# HotFireBoard.net
KiCad netlist of a schematic drawn in EAGLE
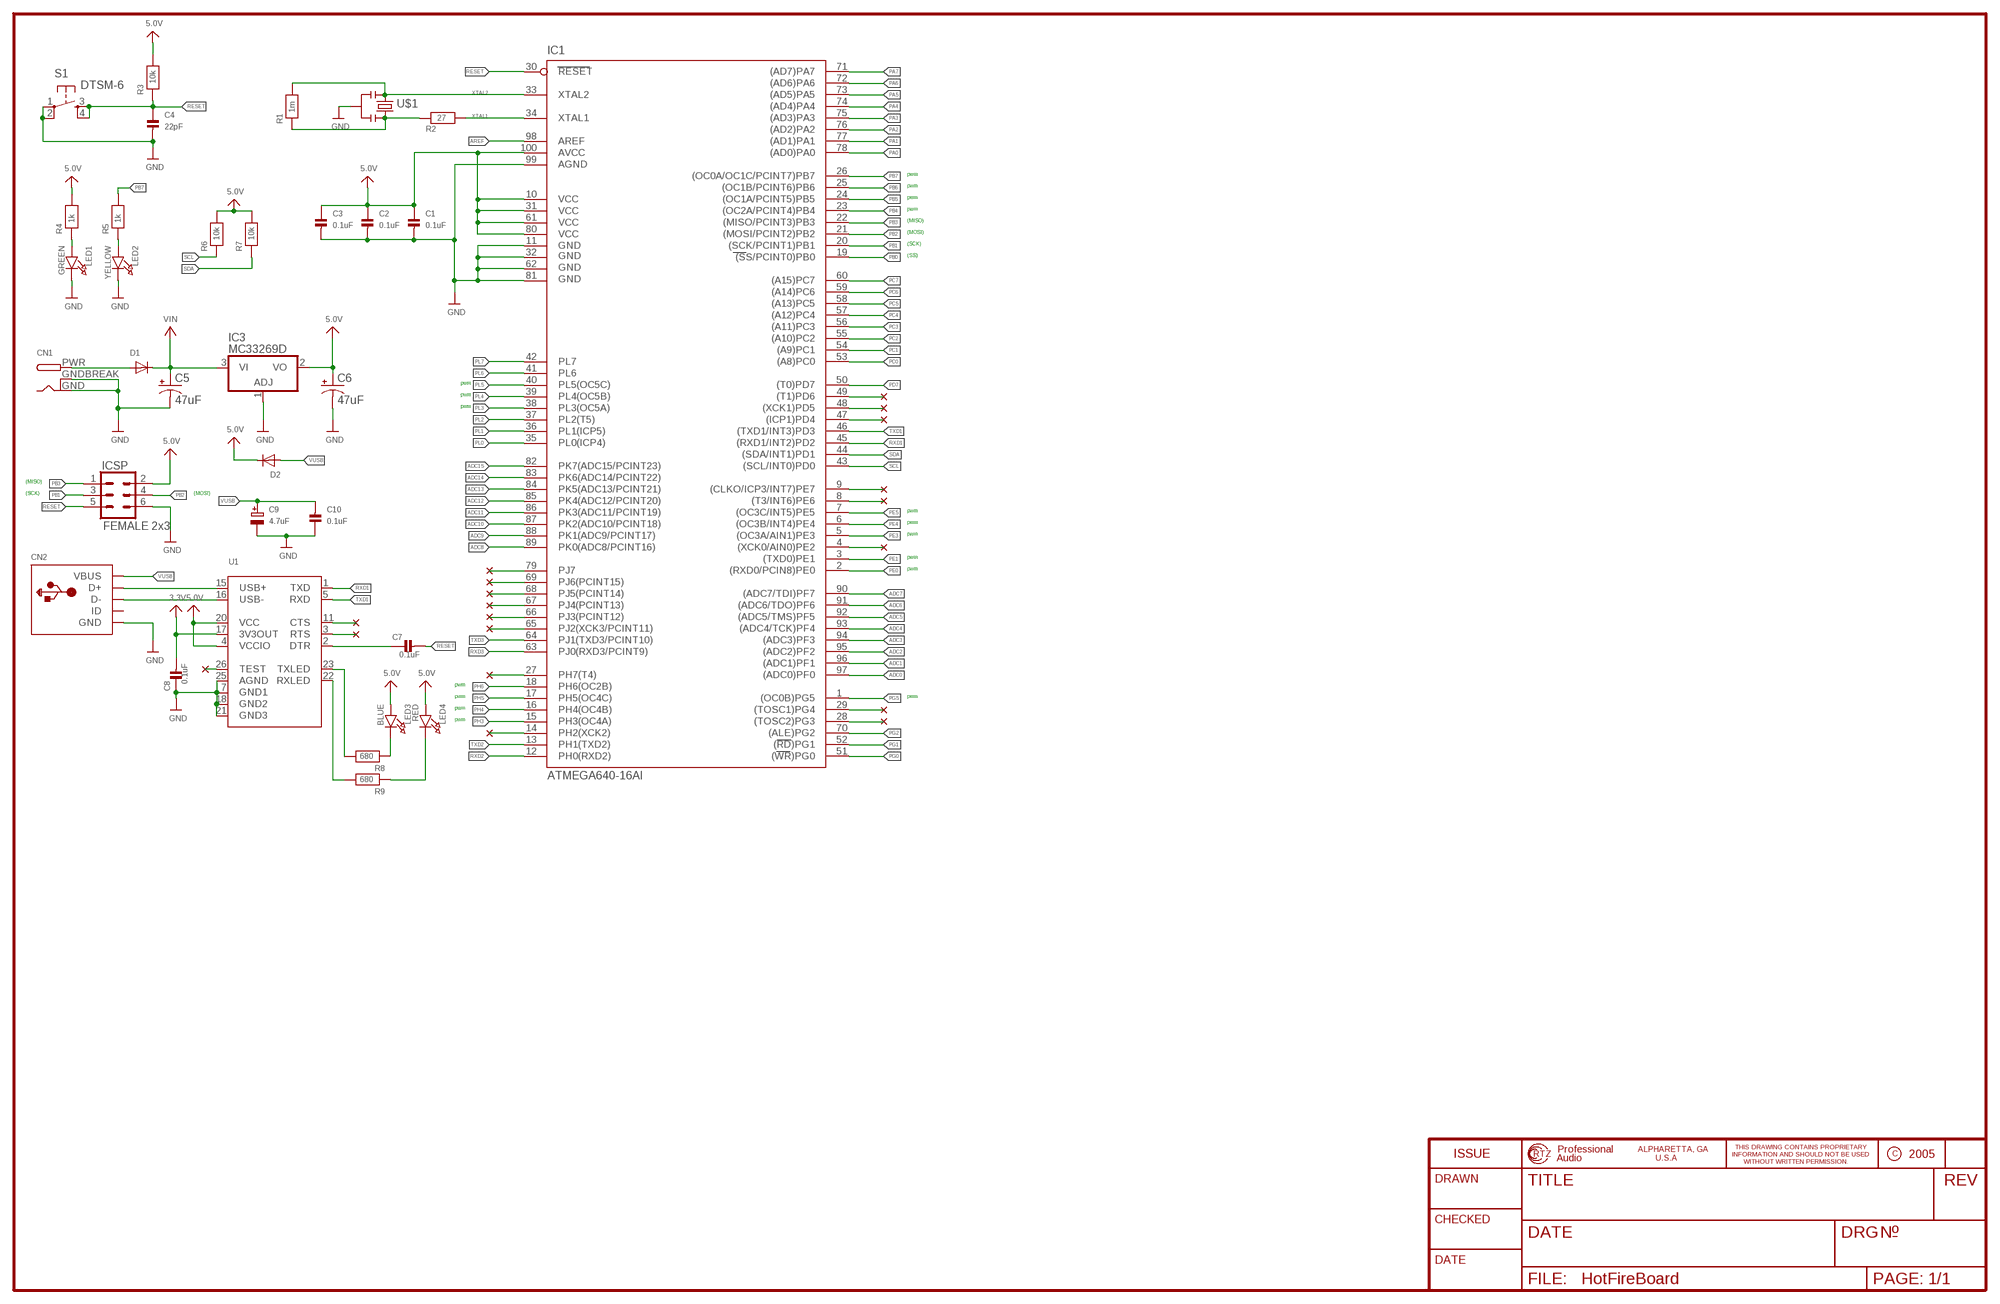
[diagram p0: schematic, sheet 1]

(export (version "E")
  (design (tool "Eeschema 10.0.6"))
  (components
    (comp (ref "C1")
      (value "0.1uF")
      (footprint "eagle-import:0805")
      (libsource (lib "eagle-import") (part "CAP_CERAMIC0805"))
    )
    (comp (ref "C2")
      (value "0.1uF")
      (footprint "eagle-import:0805")
      (libsource (lib "eagle-import") (part "CAP_CERAMIC0805"))
    )
    (comp (ref "C3")
      (value "0.1uF")
      (footprint "eagle-import:0805")
      (libsource (lib "eagle-import") (part "CAP_CERAMIC0805"))
    )
    (comp (ref "C4")
      (value "22pF")
      (footprint "eagle-import:0805")
      (libsource (lib "eagle-import") (part "CAP_CERAMIC0805"))
    )
    (comp (ref "C5")
      (value "47uF")
      (footprint "eagle-import:PANASONIC_D")
      (libsource (lib "eagle-import") (part "CPOL-USD"))
    )
    (comp (ref "C6")
      (value "47uF")
      (footprint "eagle-import:PANASONIC_D")
      (libsource (lib "eagle-import") (part "CPOL-USD"))
    )
    (comp (ref "C7")
      (value "0.1uF")
      (footprint "eagle-import:0805")
      (libsource (lib "eagle-import") (part "CAP_CERAMIC0805"))
    )
    (comp (ref "C8")
      (value "0.1uF")
      (footprint "eagle-import:0805")
      (libsource (lib "eagle-import") (part "CAP_CERAMIC0805"))
    )
    (comp (ref "C9")
      (value "4.7uF")
      (footprint "eagle-import:EIA7343-31_D-W")
      (libsource (lib "eagle-import") (part "CAP_TANTALUMD/7343_WAVE"))
    )
    (comp (ref "C10")
      (value "0.1uF")
      (footprint "eagle-import:0805")
      (libsource (lib "eagle-import") (part "CAP_CERAMIC0805"))
    )
    (comp (ref "CN1")
      (value "DCBARRELPTH")
      (footprint "eagle-import:DCJACK_2MM_PTH")
      (libsource (lib "eagle-import") (part "DCBARRELPTH"))
    )
    (comp (ref "CN2")
      (value "USBMINIB")
      (footprint "eagle-import:USB-MINIB")
      (libsource (lib "eagle-import") (part "USBMINIB"))
    )
    (comp (ref "D1")
      (value "DIODESOD-123")
      (footprint "eagle-import:SOD-123")
      (libsource (lib "eagle-import") (part "DIODESOD-123"))
    )
    (comp (ref "D2")
      (value "DIODESOD-123")
      (footprint "eagle-import:SOD-123")
      (libsource (lib "eagle-import") (part "DIODESOD-123"))
    )
    (comp (ref "IC1")
      (value "ATMEGA640-16AI")
      (footprint "eagle-import:TQFP100")
      (libsource (lib "eagle-import") (part "ATMEGAAI640-16"))
    )
    (comp (ref "IC3")
      (value "MC33269D")
      (footprint "eagle-import:DPACK")
      (libsource (lib "eagle-import") (part "MC33269?D"))
    )
    (comp (ref "ICSP")
      (value "FEMALE 2x3")
      (footprint "eagle-import:2X3")
      (libsource (lib "eagle-import") (part "CONN_03X2FEMALE"))
    )
    (comp (ref "LED1")
      (value "GREEN")
      (footprint "eagle-import:CHIPLED_0805")
      (libsource (lib "eagle-import") (part "LED0805"))
    )
    (comp (ref "LED2")
      (value "YELLOW")
      (footprint "eagle-import:CHIPLED_0805")
      (libsource (lib "eagle-import") (part "LED0805"))
    )
    (comp (ref "LED3")
      (value "BLUE")
      (footprint "eagle-import:CHIPLED_0805")
      (libsource (lib "eagle-import") (part "LED0805"))
    )
    (comp (ref "LED4")
      (value "RED")
      (footprint "eagle-import:CHIPLED_0805")
      (libsource (lib "eagle-import") (part "LED0805"))
    )
    (comp (ref "R1")
      (value "1m")
      (footprint "eagle-import:0805")
      (libsource (lib "eagle-import") (part "RESISTOR0805"))
    )
    (comp (ref "R2")
      (value "27")
      (footprint "eagle-import:0805")
      (libsource (lib "eagle-import") (part "RESISTOR0805"))
    )
    (comp (ref "R3")
      (value "10k")
      (footprint "eagle-import:0805")
      (libsource (lib "eagle-import") (part "RESISTOR0805"))
    )
    (comp (ref "R4")
      (value "1k")
      (footprint "eagle-import:0805")
      (libsource (lib "eagle-import") (part "RESISTOR0805"))
    )
    (comp (ref "R5")
      (value "1k")
      (footprint "eagle-import:0805")
      (libsource (lib "eagle-import") (part "RESISTOR0805"))
    )
    (comp (ref "R6")
      (value "10k")
      (footprint "eagle-import:0805")
      (libsource (lib "eagle-import") (part "RESISTOR0805"))
    )
    (comp (ref "R7")
      (value "10k")
      (footprint "eagle-import:0805")
      (libsource (lib "eagle-import") (part "RESISTOR0805"))
    )
    (comp (ref "R8")
      (value "680")
      (footprint "eagle-import:0805")
      (libsource (lib "eagle-import") (part "RESISTOR0805"))
    )
    (comp (ref "R9")
      (value "680")
      (footprint "eagle-import:0805")
      (libsource (lib "eagle-import") (part "RESISTOR0805"))
    )
    (comp (ref "S1")
      (value "DTSM-6")
      (footprint "eagle-import:DTSM-6")
      (libsource (lib "eagle-import") (part "DTSM-6"))
    )
    (comp (ref "U$1")
      (value "RESONATORSMD")
      (footprint "eagle-import:RESONATOR-SMD")
      (libsource (lib "eagle-import") (part "RESONATORSMD"))
    )
    (comp (ref "U$6") (value "NC") (footprint "eagle-import:NC") (libsource (lib "eagle-import") (part "NC")))
    (comp (ref "U$7") (value "NC") (footprint "eagle-import:NC") (libsource (lib "eagle-import") (part "NC")))
    (comp (ref "U$8") (value "NC") (footprint "eagle-import:NC") (libsource (lib "eagle-import") (part "NC")))
    (comp (ref "U$9") (value "NC") (footprint "eagle-import:NC") (libsource (lib "eagle-import") (part "NC")))
    (comp (ref "U$10")
      (value "NC")
      (footprint "eagle-import:NC")
      (libsource (lib "eagle-import") (part "NC"))
    )
    (comp (ref "U$11")
      (value "NC")
      (footprint "eagle-import:NC")
      (libsource (lib "eagle-import") (part "NC"))
    )
    (comp (ref "U$12")
      (value "NC")
      (footprint "eagle-import:NC")
      (libsource (lib "eagle-import") (part "NC"))
    )
    (comp (ref "U$13")
      (value "NC")
      (footprint "eagle-import:NC")
      (libsource (lib "eagle-import") (part "NC"))
    )
    (comp (ref "U$14")
      (value "NC")
      (footprint "eagle-import:NC")
      (libsource (lib "eagle-import") (part "NC"))
    )
    (comp (ref "U$15")
      (value "NC")
      (footprint "eagle-import:NC")
      (libsource (lib "eagle-import") (part "NC"))
    )
    (comp (ref "U$16")
      (value "NC")
      (footprint "eagle-import:NC")
      (libsource (lib "eagle-import") (part "NC"))
    )
    (comp (ref "U$17")
      (value "NC")
      (footprint "eagle-import:NC")
      (libsource (lib "eagle-import") (part "NC"))
    )
    (comp (ref "U$18")
      (value "NC")
      (footprint "eagle-import:NC")
      (libsource (lib "eagle-import") (part "NC"))
    )
    (comp (ref "U$19")
      (value "NC")
      (footprint "eagle-import:NC")
      (libsource (lib "eagle-import") (part "NC"))
    )
    (comp (ref "U$20")
      (value "NC")
      (footprint "eagle-import:NC")
      (libsource (lib "eagle-import") (part "NC"))
    )
    (comp (ref "U$21")
      (value "NC")
      (footprint "eagle-import:NC")
      (libsource (lib "eagle-import") (part "NC"))
    )
    (comp (ref "U$37")
      (value "NC")
      (footprint "eagle-import:NC")
      (libsource (lib "eagle-import") (part "NC"))
    )
    (comp (ref "U$38")
      (value "NC")
      (footprint "eagle-import:NC")
      (libsource (lib "eagle-import") (part "NC"))
    )
    (comp (ref "U$42")
      (value "NC")
      (footprint "eagle-import:NC")
      (libsource (lib "eagle-import") (part "NC"))
    )
    (comp (ref "U1")
      (value "FT232RLSSOP28")
      (footprint "eagle-import:SSOP28DB")
      (libsource (lib "eagle-import") (part "FT232RLSSOP28"))
    )
  )
  (nets
    (net (code "1") (name "/XTAL1") (class "Default")
      (node (ref "IC1") (pin "34") (pinfunction "XTAL1_34") (pintype "input"))
      (node (ref "R2") (pin "1") (pinfunction "1_1") (pintype "passive"))
    )
    (net (code "2") (name "/XTAL2") (class "Default")
      (node (ref "IC1") (pin "33") (pinfunction "XTAL2_33") (pintype "output"))
      (node (ref "R1") (pin "2") (pinfunction "2_2") (pintype "passive"))
      (node (ref "U$1") (pin "1") (pinfunction "1_1") (pintype "passive"))
    )
    (net (code "3") (name "3.3V") (class "Default")
      (node (ref "C8") (pin "2") (pinfunction "P$2_2") (pintype "passive"))
      (node (ref "U1") (pin "17") (pinfunction "3V3OUT_17") (pintype "power_in"))
    )
    (net (code "4") (name "5.0V") (class "Default")
      (node (ref "C1") (pin "1") (pinfunction "P$1_1") (pintype "passive"))
      (node (ref "C2") (pin "1") (pinfunction "P$1_1") (pintype "passive"))
      (node (ref "C3") (pin "1") (pinfunction "P$1_1") (pintype "passive"))
      (node (ref "C6") (pin "+") (pinfunction "+_+") (pintype "passive"))
      (node (ref "D2") (pin "C") (pinfunction "C_C") (pintype "passive"))
      (node (ref "IC1") (pin "10") (pinfunction "VCC_10") (pintype "power_in"))
      (node (ref "IC1") (pin "100") (pinfunction "AVCC_100") (pintype "power_in"))
      (node (ref "IC1") (pin "31") (pinfunction "VCC1_31") (pintype "power_in"))
      (node (ref "IC1") (pin "61") (pinfunction "VCC2_61") (pintype "power_in"))
      (node (ref "IC1") (pin "80") (pinfunction "VCC3_80") (pintype "power_in"))
      (node (ref "IC3") (pin "2") (pinfunction "VO_2") (pintype "passive"))
      (node (ref "ICSP") (pin "2") (pinfunction "2_2") (pintype "bidirectional"))
      (node (ref "LED3") (pin "A") (pinfunction "A_A") (pintype "passive"))
      (node (ref "LED4") (pin "A") (pinfunction "A_A") (pintype "passive"))
      (node (ref "R3") (pin "2") (pinfunction "2_2") (pintype "passive"))
      (node (ref "R4") (pin "2") (pinfunction "2_2") (pintype "passive"))
      (node (ref "R6") (pin "2") (pinfunction "2_2") (pintype "passive"))
      (node (ref "R7") (pin "2") (pinfunction "2_2") (pintype "passive"))
      (node (ref "U1") (pin "20") (pinfunction "VCC_20") (pintype "power_in"))
      (node (ref "U1") (pin "4") (pinfunction "VCCIO_4") (pintype "power_in"))
    )
    (net (code "5") (name "ADC0") (class "Default")
      (node (ref "IC1") (pin "97") (pinfunction "(ADC0)PF0_97") (pintype "bidirectional"))
    )
    (net (code "6") (name "ADC1") (class "Default")
      (node (ref "IC1") (pin "96") (pinfunction "(ADC1)PF1_96") (pintype "bidirectional"))
    )
    (net (code "7") (name "ADC2") (class "Default")
      (node (ref "IC1") (pin "95") (pinfunction "(ADC2)PF2_95") (pintype "bidirectional"))
    )
    (net (code "8") (name "ADC3") (class "Default")
      (node (ref "IC1") (pin "94") (pinfunction "(ADC3)PF3_94") (pintype "bidirectional"))
    )
    (net (code "9") (name "ADC4") (class "Default")
      (node (ref "IC1") (pin "93") (pinfunction "(ADC4/TCK)PF4_93") (pintype "bidirectional"))
    )
    (net (code "10") (name "ADC5") (class "Default")
      (node (ref "IC1") (pin "92") (pinfunction "(ADC5/TMS)PF5_92") (pintype "bidirectional"))
    )
    (net (code "11") (name "ADC6") (class "Default")
      (node (ref "IC1") (pin "91") (pinfunction "(ADC6/TDO)PF6_91") (pintype "bidirectional"))
    )
    (net (code "12") (name "ADC7") (class "Default")
      (node (ref "IC1") (pin "90") (pinfunction "(ADC7/TDI)PF7_90") (pintype "bidirectional"))
    )
    (net (code "13") (name "ADC8") (class "Default")
      (node (ref "IC1") (pin "89") (pinfunction "PK0(ADC8/PCINT16)_89") (pintype "bidirectional"))
    )
    (net (code "14") (name "ADC9") (class "Default")
      (node (ref "IC1") (pin "88") (pinfunction "PK1(ADC9/PCINT17)_88") (pintype "bidirectional"))
    )
    (net (code "15") (name "ADC10") (class "Default")
      (node (ref "IC1") (pin "87") (pinfunction "PK2(ADC10/PCINT18)_87") (pintype "bidirectional"))
    )
    (net (code "16") (name "ADC11") (class "Default")
      (node (ref "IC1") (pin "86") (pinfunction "PK3(ADC11/PCINT19)_86") (pintype "bidirectional"))
    )
    (net (code "17") (name "ADC12") (class "Default")
      (node (ref "IC1") (pin "85") (pinfunction "PK4(ADC12/PCINT20)_85") (pintype "bidirectional"))
    )
    (net (code "18") (name "ADC13") (class "Default")
      (node (ref "IC1") (pin "84") (pinfunction "PK5(ADC13/PCINT21)_84") (pintype "bidirectional"))
    )
    (net (code "19") (name "ADC14") (class "Default")
      (node (ref "IC1") (pin "83") (pinfunction "PK6(ADC14/PCINT22)_83") (pintype "bidirectional"))
    )
    (net (code "20") (name "ADC15") (class "Default")
      (node (ref "IC1") (pin "82") (pinfunction "PK7(ADC15/PCINT23)_82") (pintype "bidirectional"))
    )
    (net (code "21") (name "AREF") (class "Default")
      (node (ref "IC1") (pin "98") (pinfunction "AREF_98") (pintype "bidirectional"))
    )
    (net (code "22") (name "GND") (class "Default")
      (node (ref "C1") (pin "2") (pinfunction "P$2_2") (pintype "passive"))
      (node (ref "C10") (pin "1") (pinfunction "P$1_1") (pintype "passive"))
      (node (ref "C2") (pin "2") (pinfunction "P$2_2") (pintype "passive"))
      (node (ref "C3") (pin "2") (pinfunction "P$2_2") (pintype "passive"))
      (node (ref "C4") (pin "2") (pinfunction "P$2_2") (pintype "passive"))
      (node (ref "C5") (pin "-") (pinfunction "-_-") (pintype "passive"))
      (node (ref "C6") (pin "-") (pinfunction "-_-") (pintype "passive"))
      (node (ref "C8") (pin "1") (pinfunction "P$1_1") (pintype "passive"))
      (node (ref "C9") (pin "-") (pinfunction "-_-") (pintype "passive"))
      (node (ref "CN1") (pin "GND") (pinfunction "GND_GND") (pintype "power_in"))
      (node (ref "CN1") (pin "GNDBREAK") (pinfunction "GNDBREAK_GNDBREAK") (pintype "power_in"))
      (node (ref "CN2") (pin "GND") (pinfunction "GND_GND") (pintype "power_in"))
      (node (ref "IC1") (pin "11") (pinfunction "GND_11") (pintype "power_in"))
      (node (ref "IC1") (pin "32") (pinfunction "GND1_32") (pintype "power_in"))
      (node (ref "IC1") (pin "62") (pinfunction "GND2_62") (pintype "power_in"))
      (node (ref "IC1") (pin "81") (pinfunction "GND3_81") (pintype "power_in"))
      (node (ref "IC1") (pin "99") (pinfunction "AGND_99") (pintype "power_in"))
      (node (ref "IC3") (pin "1") (pinfunction "ADJ_1") (pintype "input"))
      (node (ref "ICSP") (pin "6") (pinfunction "6_6") (pintype "bidirectional"))
      (node (ref "LED1") (pin "C") (pinfunction "C_C") (pintype "passive"))
      (node (ref "LED2") (pin "C") (pinfunction "C_C") (pintype "passive"))
      (node (ref "S1") (pin "1") (pinfunction "1_1") (pintype "passive"))
      (node (ref "S1") (pin "2") (pinfunction "2_2") (pintype "passive"))
      (node (ref "U$1") (pin "2") (pinfunction "2_2") (pintype "passive"))
      (node (ref "U1") (pin "18") (pinfunction "GND2_18") (pintype "power_in"))
      (node (ref "U1") (pin "21") (pinfunction "GND3_21") (pintype "power_in"))
      (node (ref "U1") (pin "25") (pinfunction "AGND_25") (pintype "power_in"))
      (node (ref "U1") (pin "7") (pinfunction "GND1_7") (pintype "power_in"))
    )
    (net (code "23") (name "Net-(C7-P$1)") (class "Default")
      (node (ref "C7") (pin "1") (pinfunction "P$1_1") (pintype "passive"))
      (node (ref "U1") (pin "2") (pinfunction "DTR_2") (pintype "bidirectional"))
    )
    (net (code "24") (name "Net-(CN1-PadPWR)") (class "Default")
      (node (ref "CN1") (pin "PWR") (pinfunction "PWR_PWR") (pintype "power_in"))
      (node (ref "D1") (pin "A") (pinfunction "A_A") (pintype "passive"))
    )
    (net (code "25") (name "Net-(LED1-PadA)") (class "Default")
      (node (ref "LED1") (pin "A") (pinfunction "A_A") (pintype "passive"))
      (node (ref "R4") (pin "1") (pinfunction "1_1") (pintype "passive"))
    )
    (net (code "26") (name "Net-(LED2-PadA)") (class "Default")
      (node (ref "LED2") (pin "A") (pinfunction "A_A") (pintype "passive"))
      (node (ref "R5") (pin "1") (pinfunction "1_1") (pintype "passive"))
    )
    (net (code "27") (name "Net-(LED3-PadC)") (class "Default")
      (node (ref "LED3") (pin "C") (pinfunction "C_C") (pintype "passive"))
      (node (ref "R8") (pin "1") (pinfunction "1_1") (pintype "passive"))
    )
    (net (code "28") (name "Net-(LED4-PadC)") (class "Default")
      (node (ref "LED4") (pin "C") (pinfunction "C_C") (pintype "passive"))
      (node (ref "R9") (pin "1") (pinfunction "1_1") (pintype "passive"))
    )
    (net (code "29") (name "Net-(R1-Pad1)") (class "Default")
      (node (ref "R1") (pin "1") (pinfunction "1_1") (pintype "passive"))
      (node (ref "R2") (pin "2") (pinfunction "2_2") (pintype "passive"))
      (node (ref "U$1") (pin "3") (pinfunction "3_3") (pintype "passive"))
    )
    (net (code "30") (name "Net-(U1-RXLED)") (class "Default")
      (node (ref "R9") (pin "2") (pinfunction "2_2") (pintype "passive"))
      (node (ref "U1") (pin "22") (pinfunction "RXLED_22") (pintype "bidirectional"))
    )
    (net (code "31") (name "Net-(U1-TXLED)") (class "Default")
      (node (ref "R8") (pin "2") (pinfunction "2_2") (pintype "passive"))
      (node (ref "U1") (pin "23") (pinfunction "TXLED_23") (pintype "bidirectional"))
    )
    (net (code "32") (name "Net-(U1-USB+)") (class "Default")
      (node (ref "CN2") (pin "D+") (pinfunction "D+_D+") (pintype "bidirectional"))
      (node (ref "U1") (pin "15") (pinfunction "USB+_15") (pintype "bidirectional"))
    )
    (net (code "33") (name "Net-(U1-USB-)") (class "Default")
      (node (ref "CN2") (pin "D-") (pinfunction "D-_D-") (pintype "bidirectional"))
      (node (ref "U1") (pin "16") (pinfunction "USB-_16") (pintype "bidirectional"))
    )
    (net (code "34") (name "PA0") (class "Default")
      (node (ref "IC1") (pin "78") (pinfunction "(AD0)PA0_78") (pintype "bidirectional"))
    )
    (net (code "35") (name "PA1") (class "Default")
      (node (ref "IC1") (pin "77") (pinfunction "(AD1)PA1_77") (pintype "bidirectional"))
    )
    (net (code "36") (name "PA2") (class "Default")
      (node (ref "IC1") (pin "76") (pinfunction "(AD2)PA2_76") (pintype "bidirectional"))
    )
    (net (code "37") (name "PA3") (class "Default")
      (node (ref "IC1") (pin "75") (pinfunction "(AD3)PA3_75") (pintype "bidirectional"))
    )
    (net (code "38") (name "PA4") (class "Default")
      (node (ref "IC1") (pin "74") (pinfunction "(AD4)PA4_74") (pintype "bidirectional"))
    )
    (net (code "39") (name "PA5") (class "Default")
      (node (ref "IC1") (pin "73") (pinfunction "(AD5)PA5_73") (pintype "bidirectional"))
    )
    (net (code "40") (name "PA6") (class "Default")
      (node (ref "IC1") (pin "72") (pinfunction "(AD6)PA6_72") (pintype "bidirectional"))
    )
    (net (code "41") (name "PA7") (class "Default")
      (node (ref "IC1") (pin "71") (pinfunction "(AD7)PA7_71") (pintype "bidirectional"))
    )
    (net (code "42") (name "PB0") (class "Default")
      (node (ref "IC1") (pin "19") (pinfunction "(SS/PCINT0)PB0_19") (pintype "bidirectional"))
    )
    (net (code "43") (name "PB1") (class "Default")
      (node (ref "IC1") (pin "20") (pinfunction "(SCK/PCINT1)PB1_20") (pintype "bidirectional"))
      (node (ref "ICSP") (pin "3") (pinfunction "3_3") (pintype "bidirectional"))
    )
    (net (code "44") (name "PB2") (class "Default")
      (node (ref "IC1") (pin "21") (pinfunction "(MOSI/PCINT2)PB2_21") (pintype "bidirectional"))
      (node (ref "ICSP") (pin "4") (pinfunction "4_4") (pintype "bidirectional"))
    )
    (net (code "45") (name "PB3") (class "Default")
      (node (ref "IC1") (pin "22") (pinfunction "(MISO/PCINT3)PB3_22") (pintype "bidirectional"))
      (node (ref "ICSP") (pin "1") (pinfunction "1_1") (pintype "bidirectional"))
    )
    (net (code "46") (name "PB4") (class "Default")
      (node (ref "IC1") (pin "23") (pinfunction "(OC2A/PCINT4)PB4_23") (pintype "bidirectional"))
    )
    (net (code "47") (name "PB5") (class "Default")
      (node (ref "IC1") (pin "24") (pinfunction "(OC1A/PCINT5)PB5_24") (pintype "bidirectional"))
    )
    (net (code "48") (name "PB6") (class "Default")
      (node (ref "IC1") (pin "25") (pinfunction "(OC1B/PCINT6)PB6_25") (pintype "bidirectional"))
    )
    (net (code "49") (name "PB7") (class "Default")
      (node (ref "IC1") (pin "26") (pinfunction "(OC0A/OC1C/PCINT7)PB7_26") (pintype "bidirectional"))
      (node (ref "R5") (pin "2") (pinfunction "2_2") (pintype "passive"))
    )
    (net (code "50") (name "PC0") (class "Default")
      (node (ref "IC1") (pin "53") (pinfunction "(A8)PC0_53") (pintype "bidirectional"))
    )
    (net (code "51") (name "PC1") (class "Default")
      (node (ref "IC1") (pin "54") (pinfunction "(A9)PC1_54") (pintype "bidirectional"))
    )
    (net (code "52") (name "PC2") (class "Default")
      (node (ref "IC1") (pin "55") (pinfunction "(A10)PC2_55") (pintype "bidirectional"))
    )
    (net (code "53") (name "PC3") (class "Default")
      (node (ref "IC1") (pin "56") (pinfunction "(A11)PC3_56") (pintype "bidirectional"))
    )
    (net (code "54") (name "PC4") (class "Default")
      (node (ref "IC1") (pin "57") (pinfunction "(A12)PC4_57") (pintype "bidirectional"))
    )
    (net (code "55") (name "PC5") (class "Default")
      (node (ref "IC1") (pin "58") (pinfunction "(A13)PC5_58") (pintype "bidirectional"))
    )
    (net (code "56") (name "PC6") (class "Default")
      (node (ref "IC1") (pin "59") (pinfunction "(A14)PC6_59") (pintype "bidirectional"))
    )
    (net (code "57") (name "PC7") (class "Default")
      (node (ref "IC1") (pin "60") (pinfunction "(A15)PC7_60") (pintype "bidirectional"))
    )
    (net (code "58") (name "PD7") (class "Default")
      (node (ref "IC1") (pin "50") (pinfunction "(T0)PD7_50") (pintype "bidirectional"))
    )
    (net (code "59") (name "PE0") (class "Default")
      (node (ref "IC1") (pin "2") (pinfunction "(RXD0/PCIN8)PE0_2") (pintype "bidirectional"))
    )
    (net (code "60") (name "PE1") (class "Default")
      (node (ref "IC1") (pin "3") (pinfunction "(TXD0)PE1_3") (pintype "bidirectional"))
    )
    (net (code "61") (name "PE3") (class "Default")
      (node (ref "IC1") (pin "5") (pinfunction "(OC3A/AIN1)PE3_5") (pintype "bidirectional"))
    )
    (net (code "62") (name "PE4") (class "Default")
      (node (ref "IC1") (pin "6") (pinfunction "(OC3B/INT4)PE4_6") (pintype "bidirectional"))
    )
    (net (code "63") (name "PE5") (class "Default")
      (node (ref "IC1") (pin "7") (pinfunction "(OC3C/INT5)PE5_7") (pintype "bidirectional"))
    )
    (net (code "64") (name "PG0") (class "Default")
      (node (ref "IC1") (pin "51") (pinfunction "(WR)PG0_51") (pintype "bidirectional"))
    )
    (net (code "65") (name "PG1") (class "Default")
      (node (ref "IC1") (pin "52") (pinfunction "(RD)PG1_52") (pintype "bidirectional"))
    )
    (net (code "66") (name "PG2") (class "Default")
      (node (ref "IC1") (pin "70") (pinfunction "(ALE)PG2_70") (pintype "bidirectional"))
    )
    (net (code "67") (name "PG5") (class "Default")
      (node (ref "IC1") (pin "1") (pinfunction "(OC0B)PG5_1") (pintype "bidirectional"))
    )
    (net (code "68") (name "PH3") (class "Default")
      (node (ref "IC1") (pin "15") (pinfunction "PH3(OC4A)_15") (pintype "bidirectional"))
    )
    (net (code "69") (name "PH4") (class "Default")
      (node (ref "IC1") (pin "16") (pinfunction "PH4(OC4B)_16") (pintype "bidirectional"))
    )
    (net (code "70") (name "PH5") (class "Default")
      (node (ref "IC1") (pin "17") (pinfunction "PH5(OC4C)_17") (pintype "bidirectional"))
    )
    (net (code "71") (name "PH6") (class "Default")
      (node (ref "IC1") (pin "18") (pinfunction "PH6(OC2B)_18") (pintype "bidirectional"))
    )
    (net (code "72") (name "PL0") (class "Default")
      (node (ref "IC1") (pin "35") (pinfunction "PL0(ICP4)_35") (pintype "bidirectional"))
    )
    (net (code "73") (name "PL1") (class "Default")
      (node (ref "IC1") (pin "36") (pinfunction "PL1(ICP5)_36") (pintype "bidirectional"))
    )
    (net (code "74") (name "PL2") (class "Default")
      (node (ref "IC1") (pin "37") (pinfunction "PL2(T5)_37") (pintype "bidirectional"))
    )
    (net (code "75") (name "PL3") (class "Default")
      (node (ref "IC1") (pin "38") (pinfunction "PL3(OC5A)_38") (pintype "bidirectional"))
    )
    (net (code "76") (name "PL4") (class "Default")
      (node (ref "IC1") (pin "39") (pinfunction "PL4(OC5B)_39") (pintype "bidirectional"))
    )
    (net (code "77") (name "PL5") (class "Default")
      (node (ref "IC1") (pin "40") (pinfunction "PL5(OC5C)_40") (pintype "bidirectional"))
    )
    (net (code "78") (name "PL6") (class "Default")
      (node (ref "IC1") (pin "41") (pinfunction "PL6_41") (pintype "bidirectional"))
    )
    (net (code "79") (name "PL7") (class "Default")
      (node (ref "IC1") (pin "42") (pinfunction "PL7_42") (pintype "bidirectional"))
    )
    (net (code "80") (name "RESET") (class "Default")
      (node (ref "C4") (pin "1") (pinfunction "P$1_1") (pintype "passive"))
      (node (ref "C7") (pin "2") (pinfunction "P$2_2") (pintype "passive"))
      (node (ref "IC1") (pin "30") (pinfunction "RESET_30") (pintype "input"))
      (node (ref "ICSP") (pin "5") (pinfunction "5_5") (pintype "bidirectional"))
      (node (ref "R3") (pin "1") (pinfunction "1_1") (pintype "passive"))
      (node (ref "S1") (pin "3") (pinfunction "3_3") (pintype "passive"))
      (node (ref "S1") (pin "4") (pinfunction "4_4") (pintype "passive"))
    )
    (net (code "81") (name "RXD1") (class "Default")
      (node (ref "IC1") (pin "45") (pinfunction "(RXD1/INT2)PD2_45") (pintype "bidirectional"))
      (node (ref "U1") (pin "1") (pinfunction "TXD_1") (pintype "output"))
    )
    (net (code "82") (name "RXD2") (class "Default")
      (node (ref "IC1") (pin "12") (pinfunction "PH0(RXD2)_12") (pintype "bidirectional"))
    )
    (net (code "83") (name "RXD3") (class "Default")
      (node (ref "IC1") (pin "63") (pinfunction "PJ0(RXD3/PCINT9)_63") (pintype "bidirectional"))
    )
    (net (code "84") (name "SCL") (class "Default")
      (node (ref "IC1") (pin "43") (pinfunction "(SCL/INT0)PD0_43") (pintype "bidirectional"))
      (node (ref "R6") (pin "1") (pinfunction "1_1") (pintype "passive"))
    )
    (net (code "85") (name "SDA") (class "Default")
      (node (ref "IC1") (pin "44") (pinfunction "(SDA/INT1)PD1_44") (pintype "bidirectional"))
      (node (ref "R7") (pin "1") (pinfunction "1_1") (pintype "passive"))
    )
    (net (code "86") (name "TXD1") (class "Default")
      (node (ref "IC1") (pin "46") (pinfunction "(TXD1/INT3)PD3_46") (pintype "bidirectional"))
      (node (ref "U1") (pin "5") (pinfunction "RXD_5") (pintype "input"))
    )
    (net (code "87") (name "TXD2") (class "Default")
      (node (ref "IC1") (pin "13") (pinfunction "PH1(TXD2)_13") (pintype "bidirectional"))
    )
    (net (code "88") (name "TXD3") (class "Default")
      (node (ref "IC1") (pin "64") (pinfunction "PJ1(TXD3/PCINT10)_64") (pintype "bidirectional"))
    )
    (net (code "89") (name "VIN") (class "Default")
      (node (ref "C5") (pin "+") (pinfunction "+_+") (pintype "passive"))
      (node (ref "D1") (pin "C") (pinfunction "C_C") (pintype "passive"))
      (node (ref "IC3") (pin "3") (pinfunction "VI_3") (pintype "input"))
    )
    (net (code "90") (name "VUSB") (class "Default")
      (node (ref "C10") (pin "2") (pinfunction "P$2_2") (pintype "passive"))
      (node (ref "C9") (pin "+") (pinfunction "+_+") (pintype "passive"))
      (node (ref "CN2") (pin "VBUS") (pinfunction "VBUS_VBUS") (pintype "power_in"))
      (node (ref "D2") (pin "A") (pinfunction "A_A") (pintype "passive"))
    )
    (net (code "91") (name "unconnected-(CN2-PadID)") (class "Default")
      (node (ref "CN2") (pin "ID") (pinfunction "ID_ID") (pintype "bidirectional"))
    )
    (net (code "92") (name "unconnected-(IC1-(CLKO{slash}ICP3{slash}INT7)PE7-Pad9)") (class "Default")
      (node (ref "IC1") (pin "9") (pinfunction "(CLKO/ICP3/INT7)PE7_9") (pintype "bidirectional"))
    )
    (net (code "93") (name "unconnected-(IC1-(ICP1)PD4-Pad47)") (class "Default")
      (node (ref "IC1") (pin "47") (pinfunction "(ICP1)PD4_47") (pintype "bidirectional"))
    )
    (net (code "94") (name "unconnected-(IC1-(T1)PD6-Pad49)") (class "Default")
      (node (ref "IC1") (pin "49") (pinfunction "(T1)PD6_49") (pintype "bidirectional"))
    )
    (net (code "95") (name "unconnected-(IC1-(T3{slash}INT6)PE6-Pad8)") (class "Default")
      (node (ref "IC1") (pin "8") (pinfunction "(T3/INT6)PE6_8") (pintype "bidirectional"))
    )
    (net (code "96") (name "unconnected-(IC1-(TOSC1)PG4-Pad29)") (class "Default")
      (node (ref "IC1") (pin "29") (pinfunction "(TOSC1)PG4_29") (pintype "bidirectional"))
    )
    (net (code "97") (name "unconnected-(IC1-(TOSC2)PG3-Pad28)") (class "Default")
      (node (ref "IC1") (pin "28") (pinfunction "(TOSC2)PG3_28") (pintype "bidirectional"))
    )
    (net (code "98") (name "unconnected-(IC1-(XCK0{slash}AIN0)PE2-Pad4)") (class "Default")
      (node (ref "IC1") (pin "4") (pinfunction "(XCK0/AIN0)PE2_4") (pintype "bidirectional"))
    )
    (net (code "99") (name "unconnected-(IC1-(XCK1)PD5-Pad48)") (class "Default")
      (node (ref "IC1") (pin "48") (pinfunction "(XCK1)PD5_48") (pintype "bidirectional"))
    )
    (net (code "100") (name "unconnected-(IC1-PH2(XCK2)-Pad14)") (class "Default")
      (node (ref "IC1") (pin "14") (pinfunction "PH2(XCK2)_14") (pintype "bidirectional"))
    )
    (net (code "101") (name "unconnected-(IC1-PH7(T4)-Pad27)") (class "Default")
      (node (ref "IC1") (pin "27") (pinfunction "PH7(T4)_27") (pintype "bidirectional"))
    )
    (net (code "102") (name "unconnected-(IC1-PJ2(XCK3{slash}PCINT11)-Pad65)") (class "Default")
      (node (ref "IC1") (pin "65") (pinfunction "PJ2(XCK3/PCINT11)_65") (pintype "bidirectional"))
    )
    (net (code "103") (name "unconnected-(IC1-PJ3(PCINT12)-Pad66)") (class "Default")
      (node (ref "IC1") (pin "66") (pinfunction "PJ3(PCINT12)_66") (pintype "bidirectional"))
    )
    (net (code "104") (name "unconnected-(IC1-PJ4(PCINT13)-Pad67)") (class "Default")
      (node (ref "IC1") (pin "67") (pinfunction "PJ4(PCINT13)_67") (pintype "bidirectional"))
    )
    (net (code "105") (name "unconnected-(IC1-PJ5(PCINT14)-Pad68)") (class "Default")
      (node (ref "IC1") (pin "68") (pinfunction "PJ5(PCINT14)_68") (pintype "bidirectional"))
    )
    (net (code "106") (name "unconnected-(IC1-PJ6(PCINT15)-Pad69)") (class "Default")
      (node (ref "IC1") (pin "69") (pinfunction "PJ6(PCINT15)_69") (pintype "bidirectional"))
    )
    (net (code "107") (name "unconnected-(IC1-PJ7-Pad79)") (class "Default")
      (node (ref "IC1") (pin "79") (pinfunction "PJ7_79") (pintype "bidirectional"))
    )
    (net (code "108") (name "unconnected-(U1-CTS-Pad11)") (class "Default")
      (node (ref "U1") (pin "11") (pinfunction "CTS_11") (pintype "bidirectional"))
    )
    (net (code "109") (name "unconnected-(U1-RTS-Pad3)") (class "Default")
      (node (ref "U1") (pin "3") (pinfunction "RTS_3") (pintype "bidirectional"))
    )
    (net (code "110") (name "unconnected-(U1-TEST-Pad26)") (class "Default")
      (node (ref "U1") (pin "26") (pinfunction "TEST_26") (pintype "input"))
    )
  )
)
